# ESP-8266_Datalogger.net
KiCad netlist of a schematic drawn in EAGLE
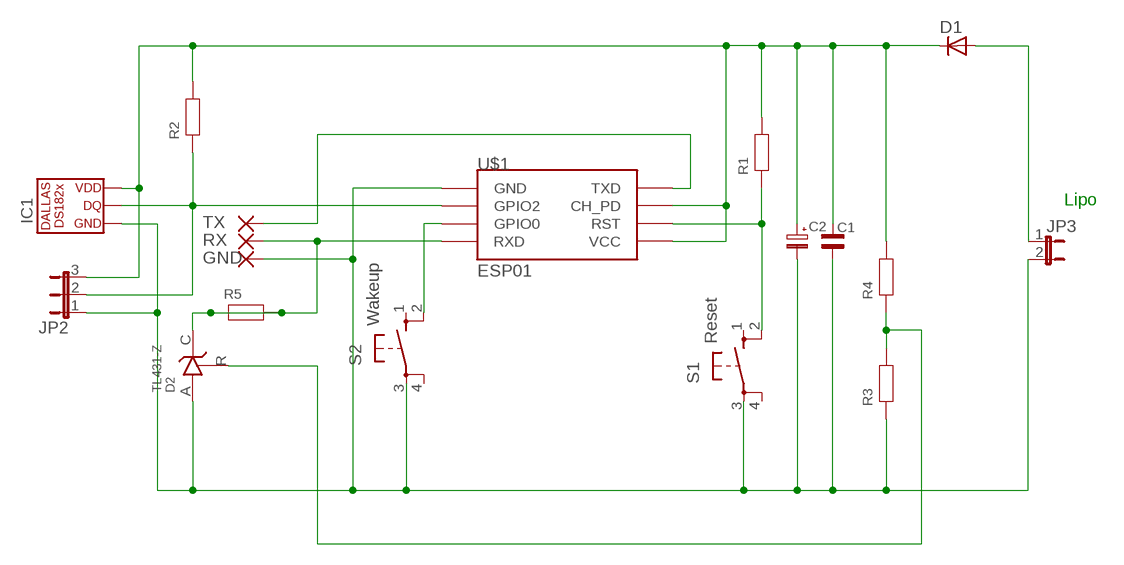
[diagram p0: schematic, sheet 1]

(export (version "E")
  (design (tool "Eeschema 10.0.6"))
  (components
    (comp (ref "C1")
      (value "C-C1206")
      (footprint "eagle-import:C1206")
      (libsource (lib "eagle-import") (part "C-C1206"))
    )
    (comp (ref "C2")
      (value "ELKO-SMC_B")
      (footprint "eagle-import:SMC_B")
      (libsource (lib "eagle-import") (part "ELKO-SMC_B"))
    )
    (comp (ref "D1")
      (value "BYS10")
      (footprint "eagle-import:SOD106A")
      (libsource (lib "eagle-import") (part "BYS10"))
    )
    (comp (ref "D2")
      (value "TL431-Z")
      (footprint "eagle-import:TO92-Z")
      (libsource (lib "eagle-import") (part "TL431-Z"))
    )
    (comp (ref "GND")
      (value "1,6/0,8")
      (footprint "eagle-import:1,6_0,8")
      (libsource (lib "eagle-import") (part "1,6/0,8"))
    )
    (comp (ref "IC1")
      (value "DS182X-L")
      (footprint "eagle-import:TO92-")
      (libsource (lib "eagle-import") (part "DS182X-L"))
    )
    (comp (ref "JP2")
      (value "JP2E")
      (footprint "eagle-import:JP2")
      (libsource (lib "eagle-import") (part "JP2E"))
    )
    (comp (ref "JP3")
      (value "JP1E")
      (footprint "eagle-import:JP1")
      (libsource (lib "eagle-import") (part "JP1E"))
    )
    (comp (ref "R1")
      (value "R-R1206")
      (footprint "eagle-import:R1206")
      (libsource (lib "eagle-import") (part "R-R1206"))
    )
    (comp (ref "R2")
      (value "R-R1206")
      (footprint "eagle-import:R1206")
      (libsource (lib "eagle-import") (part "R-R1206"))
    )
    (comp (ref "R3")
      (value "R-R1206")
      (footprint "eagle-import:R1206")
      (libsource (lib "eagle-import") (part "R-R1206"))
    )
    (comp (ref "R4")
      (value "R-R1206")
      (footprint "eagle-import:R1206")
      (libsource (lib "eagle-import") (part "R-R1206"))
    )
    (comp (ref "R5")
      (value "R400MIL")
      (footprint "eagle-import:RES400")
      (libsource (lib "eagle-import") (part "R400MIL"))
    )
    (comp (ref "RX")
      (value "1,6/0,8")
      (footprint "eagle-import:1,6_0,8")
      (libsource (lib "eagle-import") (part "1,6/0,8"))
    )
    (comp (ref "S1")
      (value "Reset")
      (footprint "eagle-import:B3F-10XX")
      (libsource (lib "eagle-import") (part "10-XX"))
    )
    (comp (ref "S2")
      (value "Wakeup")
      (footprint "eagle-import:B3F-10XX")
      (libsource (lib "eagle-import") (part "10-XX"))
    )
    (comp (ref "TX")
      (value "1,6/0,8")
      (footprint "eagle-import:1,6_0,8")
      (libsource (lib "eagle-import") (part "1,6/0,8"))
    )
    (comp (ref "U$1")
      (value "ESP01")
      (footprint "eagle-import:ESP01")
      (libsource (lib "eagle-import") (part "ESP01"))
    )
  )
  (nets
    (net (code "1") (name "Net-(C2-1)") (class "Default")
      (node (ref "C1") (pin "1") (pinfunction "1_1") (pintype "passive"))
      (node (ref "C2") (pin "+") (pinfunction "1_+") (pintype "passive"))
      (node (ref "D1") (pin "K") (pinfunction "K_K") (pintype "passive"))
      (node (ref "IC1") (pin "E") (pinfunction "3_E") (pintype "bidirectional"))
      (node (ref "JP2") (pin "3") (pinfunction "3_3") (pintype "passive"))
      (node (ref "R1") (pin "2") (pinfunction "2_2") (pintype "passive"))
      (node (ref "R2") (pin "2") (pinfunction "2_2") (pintype "passive"))
      (node (ref "R4") (pin "2") (pinfunction "2_2") (pintype "passive"))
      (node (ref "U$1") (pin "CH_PD") (pinfunction "CH_PD_CH_PD") (pintype "bidirectional"))
      (node (ref "U$1") (pin "VCC") (pinfunction "VCC_VCC") (pintype "bidirectional"))
    )
    (net (code "2") (name "Net-(C2-2)") (class "Default")
      (node (ref "C1") (pin "2") (pinfunction "2_2") (pintype "passive"))
      (node (ref "C2") (pin "-") (pinfunction "2_-") (pintype "passive"))
      (node (ref "D2") (pin "A") (pinfunction "A_A") (pintype "passive"))
      (node (ref "GND") (pin "1") (pinfunction "P_1") (pintype "passive"))
      (node (ref "IC1") (pin "C") (pinfunction "1_C") (pintype "bidirectional"))
      (node (ref "JP2") (pin "1") (pinfunction "1_1") (pintype "passive"))
      (node (ref "JP3") (pin "2") (pinfunction "2_2") (pintype "passive"))
      (node (ref "R3") (pin "1") (pinfunction "1_1") (pintype "passive"))
      (node (ref "S1") (pin "3") (pinfunction "3_3") (pintype "passive"))
      (node (ref "S2") (pin "3") (pinfunction "3_3") (pintype "passive"))
      (node (ref "U$1") (pin "GND") (pinfunction "GND_GND") (pintype "bidirectional"))
    )
    (net (code "3") (name "Net-(D1-PadA)") (class "Default")
      (node (ref "D1") (pin "A") (pinfunction "A_A") (pintype "passive"))
      (node (ref "JP3") (pin "1") (pinfunction "1_1") (pintype "passive"))
    )
    (net (code "4") (name "Net-(D2-PadR)") (class "Default")
      (node (ref "D2") (pin "R") (pinfunction "R_R") (pintype "passive"))
      (node (ref "R3") (pin "2") (pinfunction "2_2") (pintype "passive"))
      (node (ref "R4") (pin "1") (pinfunction "1_1") (pintype "passive"))
    )
    (net (code "5") (name "Net-(IC1-2)") (class "Default")
      (node (ref "IC1") (pin "B") (pinfunction "2_B") (pintype "bidirectional"))
      (node (ref "JP2") (pin "2") (pinfunction "2_2") (pintype "passive"))
      (node (ref "R2") (pin "1") (pinfunction "1_1") (pintype "passive"))
      (node (ref "U$1") (pin "GPIO2") (pinfunction "GPIO2_GPIO2") (pintype "bidirectional"))
    )
    (net (code "6") (name "Net-(R1-Pad1)") (class "Default")
      (node (ref "R1") (pin "1") (pinfunction "1_1") (pintype "passive"))
      (node (ref "S1") (pin "2") (pinfunction "2_2") (pintype "passive"))
      (node (ref "U$1") (pin "RST") (pinfunction "RST_RST") (pintype "bidirectional"))
    )
    (net (code "7") (name "Net-(RX-P)") (class "Default")
      (node (ref "D2") (pin "C") (pinfunction "C_C") (pintype "passive"))
      (node (ref "R5") (pin "1") (pinfunction "1_1") (pintype "passive"))
      (node (ref "R5") (pin "2") (pinfunction "2_2") (pintype "passive"))
      (node (ref "RX") (pin "1") (pinfunction "P_1") (pintype "passive"))
      (node (ref "U$1") (pin "RX") (pinfunction "RXD_RX") (pintype "bidirectional"))
    )
    (net (code "8") (name "Net-(S2-Pad2)") (class "Default")
      (node (ref "S2") (pin "2") (pinfunction "2_2") (pintype "passive"))
      (node (ref "U$1") (pin "GPIO0") (pinfunction "GPIO0_GPIO0") (pintype "bidirectional"))
    )
    (net (code "9") (name "Net-(TX-P)") (class "Default")
      (node (ref "TX") (pin "1") (pinfunction "P_1") (pintype "passive"))
      (node (ref "U$1") (pin "TX") (pinfunction "TXD_TX") (pintype "bidirectional"))
    )
    (net (code "10") (name "unconnected-(S1-Pad1)") (class "Default")
      (node (ref "S1") (pin "1") (pinfunction "1_1") (pintype "passive"))
    )
    (net (code "11") (name "unconnected-(S1-Pad4)") (class "Default")
      (node (ref "S1") (pin "4") (pinfunction "4_4") (pintype "passive"))
    )
    (net (code "12") (name "unconnected-(S2-Pad1)") (class "Default")
      (node (ref "S2") (pin "1") (pinfunction "1_1") (pintype "passive"))
    )
    (net (code "13") (name "unconnected-(S2-Pad4)") (class "Default")
      (node (ref "S2") (pin "4") (pinfunction "4_4") (pintype "passive"))
    )
  )
)
